# zhengbingquant_Nano_V1.net
KiCad netlist of a schematic drawn in EasyEDA Pro
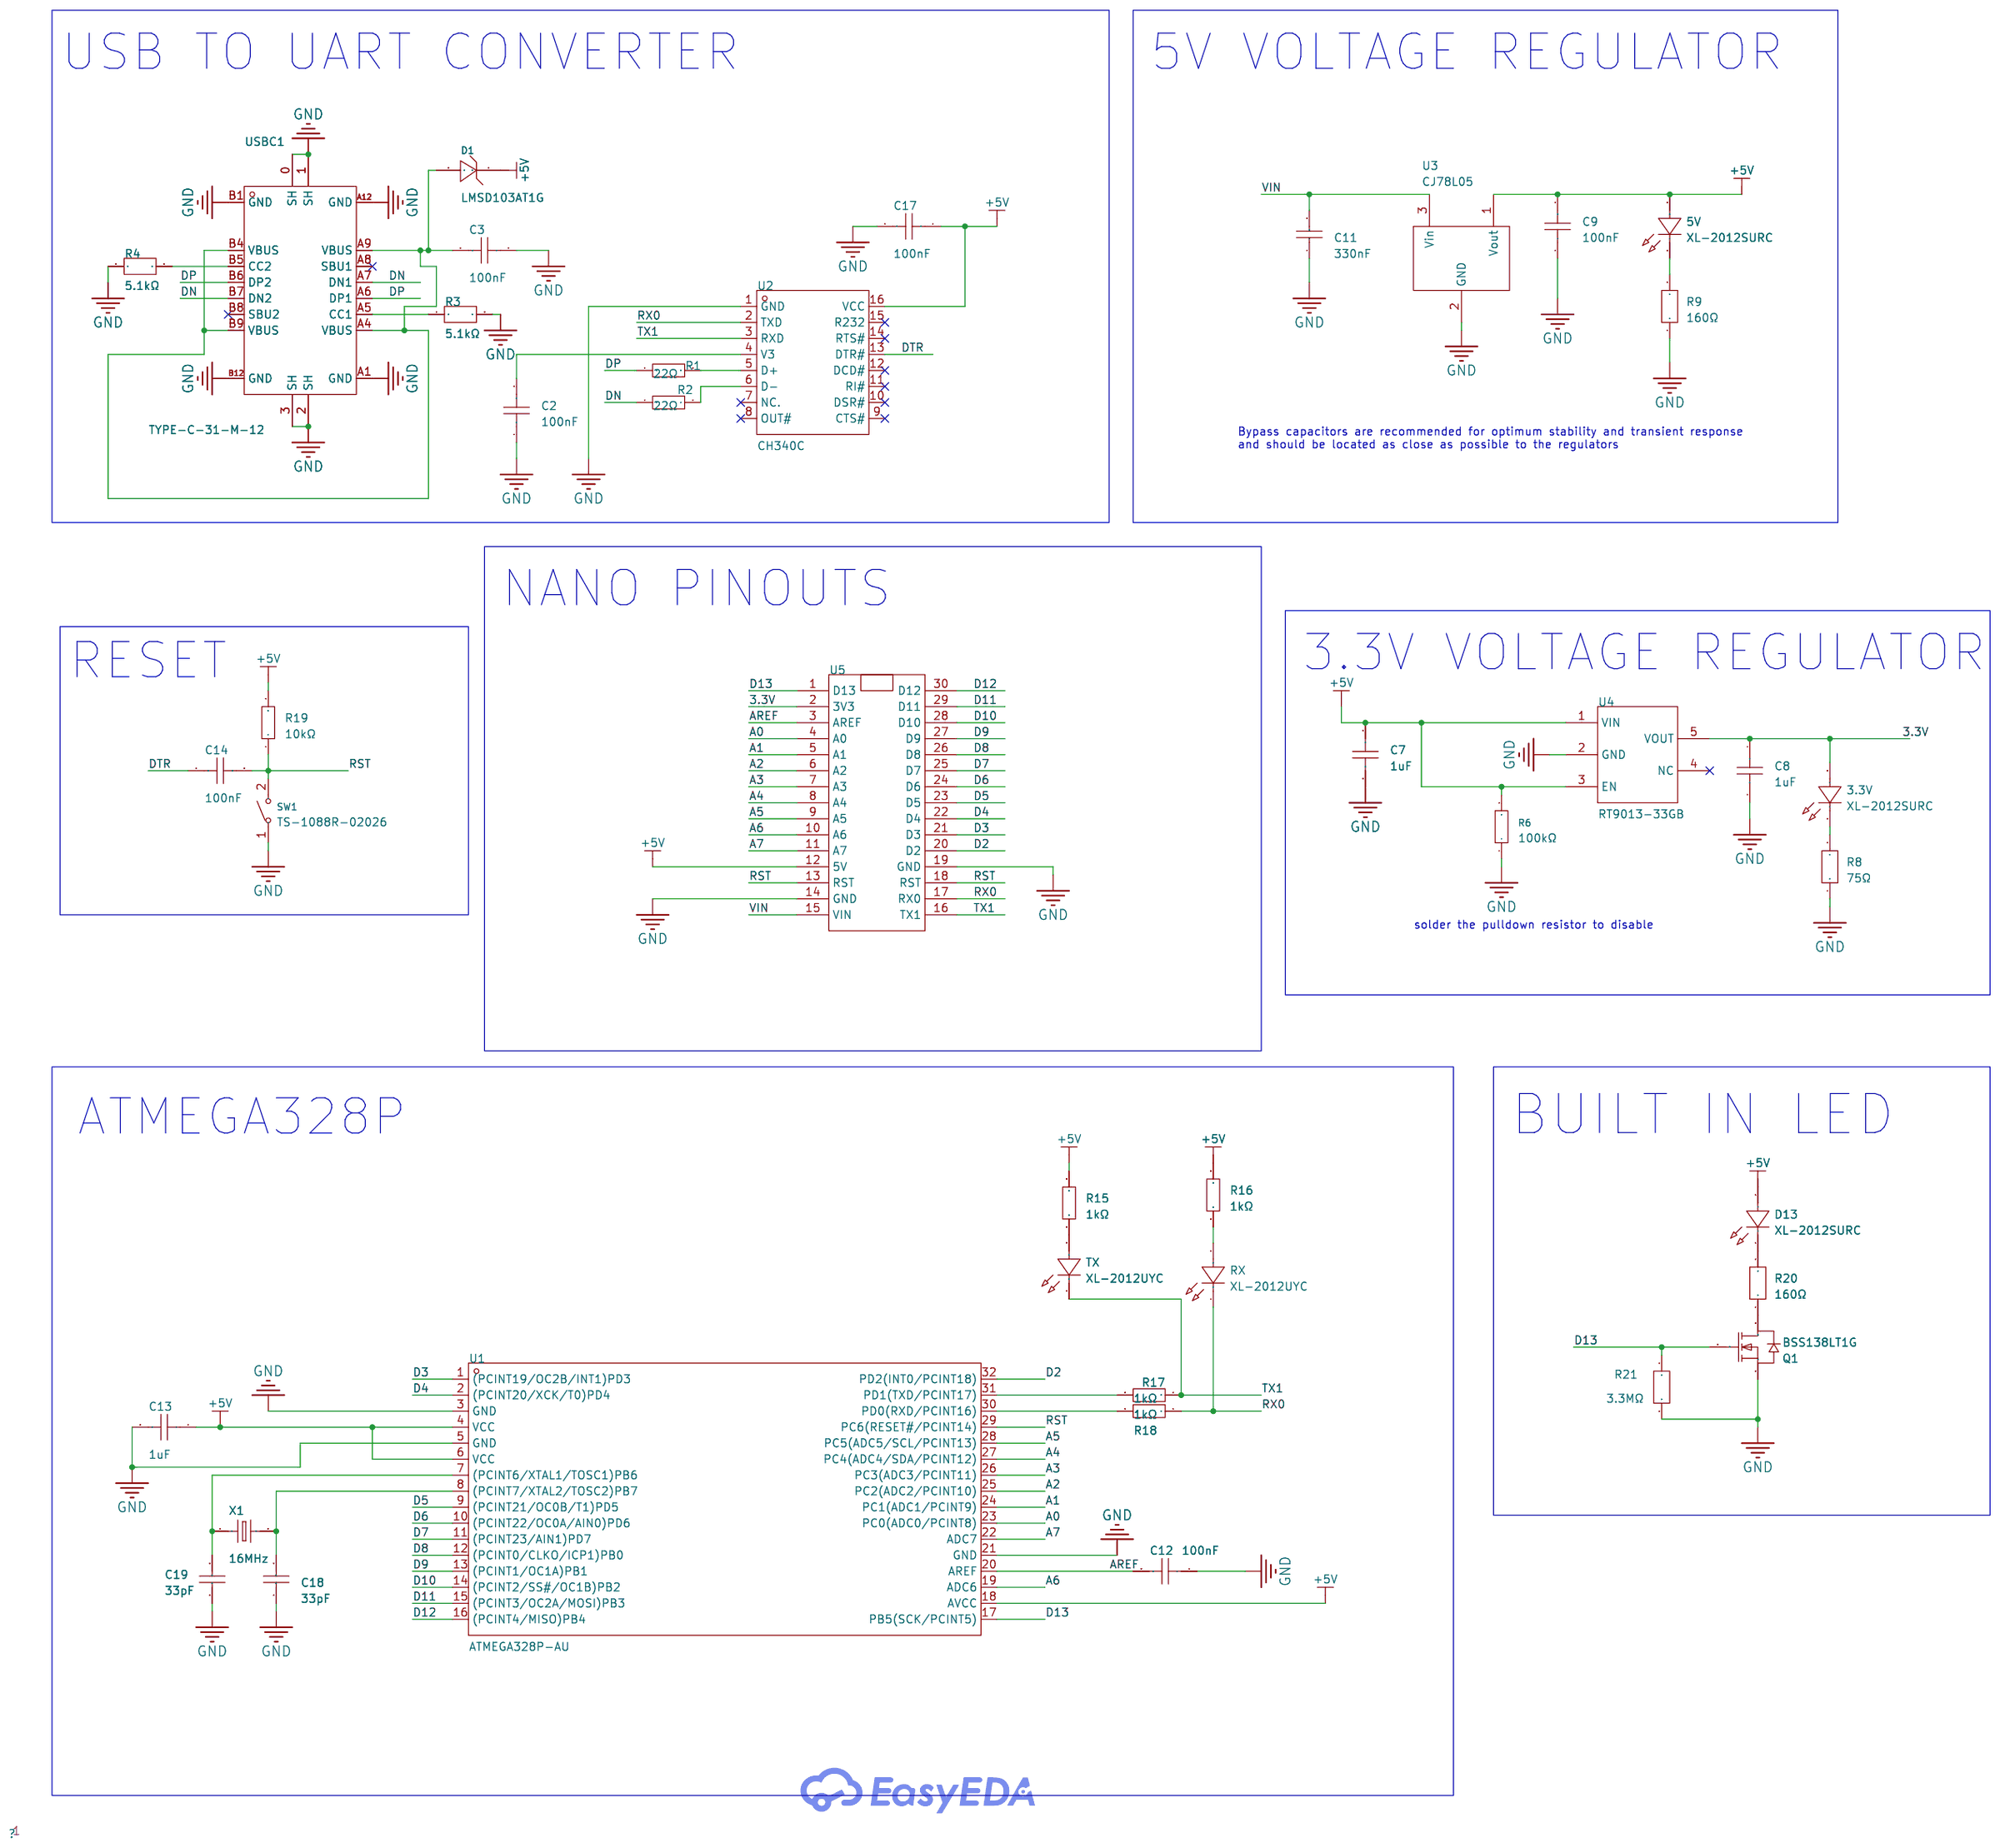
[diagram p0: schematic sheet]

(export (version "E")
  (design (tool "Eeschema 10.0.6"))
  (components
    (comp (ref "3.3V")
      (value "XL-2012SURC")
      (footprint "easyedapro:LED0805-RD_RED")
      (fields (field (name "Manufacturer") "XINGLIGHT(成兴光)"))
      (libsource (lib "easyedapro") (part "XL-2012SURC"))
    )
    (comp (ref "5V")
      (value "XL-2012SURC")
      (footprint "easyedapro:LED0805-RD_RED")
      (fields (field (name "Manufacturer") "XINGLIGHT(成兴光)"))
      (libsource (lib "easyedapro") (part "XL-2012SURC"))
    )
    (comp (ref "C2")
      (value "100nF")
      (footprint "easyedapro:C0805")
      (fields
        (field (name "Manufacturer Part") "CL21B104KBCWPNC")
        (field (name "Manufacturer") "SAMSUNG(三星)")
      )
      (libsource (lib "easyedapro") (part "CL21B104KBCWPNC"))
    )
    (comp (ref "C3")
      (value "100nF")
      (footprint "easyedapro:C0805")
      (fields
        (field (name "Manufacturer Part") "CL21B104KBCWPNC")
        (field (name "Manufacturer") "SAMSUNG(三星)")
      )
      (libsource (lib "easyedapro") (part "CL21B104KBCWPNC"))
    )
    (comp (ref "C7")
      (value "1uF")
      (footprint "easyedapro:C0805")
      (description "Capacitance:1uF Tolerance:±10% Tolerance:±10% Voltage Rating:50V Temperature Coefficient:X5R")
      (fields
        (field (name "Manufacturer Part") "UMK212BJ105KG-T")
        (field (name "Manufacturer") "TAIYO YUDEN(太诱)")
      )
      (libsource (lib "easyedapro") (part "UMK212BJ105KG-T"))
    )
    (comp (ref "C8")
      (value "1uF")
      (footprint "easyedapro:C0805")
      (description "Capacitance:1uF Tolerance:±10% Tolerance:±10% Voltage Rating:50V Temperature Coefficient:X5R")
      (fields
        (field (name "Manufacturer Part") "UMK212BJ105KG-T")
        (field (name "Manufacturer") "TAIYO YUDEN(太诱)")
      )
      (libsource (lib "easyedapro") (part "UMK212BJ105KG-T"))
    )
    (comp (ref "C9")
      (value "100nF")
      (footprint "easyedapro:C0805")
      (fields
        (field (name "Manufacturer Part") "CL21B104KBCWPNC")
        (field (name "Manufacturer") "SAMSUNG(三星)")
      )
      (libsource (lib "easyedapro") (part "CL21B104KBCWPNC"))
    )
    (comp (ref "C11")
      (value "330nF")
      (footprint "easyedapro:C0805")
      (fields
        (field (name "Manufacturer Part") "CL21B334KBFNNNE")
        (field (name "Manufacturer") "SAMSUNG(三星)")
      )
      (libsource (lib "easyedapro") (part "CL21B334KBFNNNE"))
    )
    (comp (ref "C12")
      (value "100nF")
      (footprint "easyedapro:C0805")
      (fields
        (field (name "Manufacturer Part") "CL21B104KBCWPNC")
        (field (name "Manufacturer") "SAMSUNG(三星)")
      )
      (libsource (lib "easyedapro") (part "CL21B104KBCWPNC"))
    )
    (comp (ref "C13")
      (value "1uF")
      (footprint "easyedapro:C0805")
      (description "Capacitance:1uF Tolerance:±10% Tolerance:±10% Voltage Rating:50V Temperature Coefficient:X5R")
      (fields
        (field (name "Manufacturer Part") "UMK212BJ105KG-T")
        (field (name "Manufacturer") "TAIYO YUDEN(太诱)")
      )
      (libsource (lib "easyedapro") (part "UMK212BJ105KG-T"))
    )
    (comp (ref "C14")
      (value "100nF")
      (footprint "easyedapro:C0805")
      (fields
        (field (name "Manufacturer Part") "CL21B104KBCWPNC")
        (field (name "Manufacturer") "SAMSUNG(三星)")
      )
      (libsource (lib "easyedapro") (part "CL21B104KBCWPNC"))
    )
    (comp (ref "C17")
      (value "100nF")
      (footprint "easyedapro:C0805")
      (fields
        (field (name "Manufacturer Part") "CL21B104KBCWPNC")
        (field (name "Manufacturer") "SAMSUNG(三星)")
      )
      (libsource (lib "easyedapro") (part "CL21B104KBCWPNC"))
    )
    (comp (ref "C18")
      (value "33pF")
      (footprint "easyedapro:C0805")
      (fields (field (name "Manufacturer Part") "0805CG330J500NT") (field (name "Manufacturer") "FH(风华)"))
      (libsource (lib "easyedapro") (part "0805CG330J500NT"))
    )
    (comp (ref "C19")
      (value "33pF")
      (footprint "easyedapro:C0805")
      (fields (field (name "Manufacturer Part") "0805CG330J500NT") (field (name "Manufacturer") "FH(风华)"))
      (libsource (lib "easyedapro") (part "0805CG330J500NT"))
    )
    (comp (ref "D1")
      (value "LMSD103AT1G")
      (footprint "easyedapro:SOD-123_L2.8-W1.8-LS3.7-RD")
      (fields (field (name "Manufacturer") "LRC(乐山无线电)"))
      (libsource (lib "easyedapro") (part "LMSD103AT1G"))
    )
    (comp (ref "D13")
      (value "XL-2012SURC")
      (footprint "easyedapro:LED0805-RD_RED")
      (fields (field (name "Manufacturer") "XINGLIGHT(成兴光)"))
      (libsource (lib "easyedapro") (part "XL-2012SURC"))
    )
    (comp (ref "Q1")
      (value "BSS138LT1G")
      (footprint "easyedapro:SOT-23-3_L2.9-W1.6-P1.90-LS2.8-BR")
      (fields (field (name "Manufacturer") "onsemi(安森美)"))
      (libsource (lib "easyedapro") (part "BSS138LT1G"))
    )
    (comp (ref "R1")
      (value "22Ω")
      (footprint "easyedapro:R0603")
      (fields
        (field (name "Manufacturer Part") "0603WAF220JT5E")
        (field (name "Manufacturer") "UNI-ROYAL(厚声)")
      )
      (libsource (lib "easyedapro") (part "0603WAF220JT5E"))
    )
    (comp (ref "R2")
      (value "22Ω")
      (footprint "easyedapro:R0603")
      (fields
        (field (name "Manufacturer Part") "0603WAF220JT5E")
        (field (name "Manufacturer") "UNI-ROYAL(厚声)")
      )
      (libsource (lib "easyedapro") (part "0603WAF220JT5E"))
    )
    (comp (ref "R3")
      (value "5.1kΩ")
      (footprint "easyedapro:R0603")
      (fields (field (name "Manufacturer Part") "FRC0603F5101TS") (field (name "Manufacturer") "FOJAN(富捷)"))
      (libsource (lib "easyedapro") (part "FRC0603F5101TS"))
    )
    (comp (ref "R4")
      (value "5.1kΩ")
      (footprint "easyedapro:R0603")
      (fields (field (name "Manufacturer Part") "FRC0603F5101TS") (field (name "Manufacturer") "FOJAN(富捷)"))
      (libsource (lib "easyedapro") (part "FRC0603F5101TS"))
    )
    (comp (ref "R6")
      (value "100kΩ")
      (footprint "easyedapro:R0805")
      (fields
        (field (name "Manufacturer Part") "0805W8F1003T5E")
        (field (name "Manufacturer") "UNI-ROYAL(厚声)")
      )
      (libsource (lib "easyedapro") (part "0805W8F1003T5E_C149504"))
    )
    (comp (ref "R8")
      (value "75Ω")
      (footprint "easyedapro:R0805")
      (fields (field (name "Manufacturer Part") "FRC0805J750 TS") (field (name "Manufacturer") "FOJAN(富捷)"))
      (libsource (lib "easyedapro") (part "FRC0805J750 TS"))
    )
    (comp (ref "R9")
      (value "160Ω")
      (footprint "easyedapro:R0805")
      (fields (field (name "Manufacturer Part") "FRC0805F1600TS") (field (name "Manufacturer") "FOJAN(富捷)"))
      (libsource (lib "easyedapro") (part "FRC0805F1600TS"))
    )
    (comp (ref "R15")
      (value "1kΩ")
      (footprint "easyedapro:R0805")
      (fields (field (name "Manufacturer Part") "RC0805FR-071KL") (field (name "Manufacturer") "YAGEO(国巨)"))
      (libsource (lib "easyedapro") (part "RC0805FR-071KL"))
    )
    (comp (ref "R16")
      (value "1kΩ")
      (footprint "easyedapro:R0805")
      (fields (field (name "Manufacturer Part") "RC0805FR-071KL") (field (name "Manufacturer") "YAGEO(国巨)"))
      (libsource (lib "easyedapro") (part "RC0805FR-071KL"))
    )
    (comp (ref "R17")
      (value "1kΩ")
      (footprint "easyedapro:R0805")
      (fields (field (name "Manufacturer Part") "RC0805FR-071KL") (field (name "Manufacturer") "YAGEO(国巨)"))
      (libsource (lib "easyedapro") (part "RC0805FR-071KL"))
    )
    (comp (ref "R18")
      (value "1kΩ")
      (footprint "easyedapro:R0805")
      (fields (field (name "Manufacturer Part") "RC0805FR-071KL") (field (name "Manufacturer") "YAGEO(国巨)"))
      (libsource (lib "easyedapro") (part "RC0805FR-071KL"))
    )
    (comp (ref "R19")
      (value "10kΩ")
      (footprint "easyedapro:R0805")
      (fields (field (name "Manufacturer Part") "RC0805FR-0710KL") (field (name "Manufacturer") "YAGEO(国巨)"))
      (libsource (lib "easyedapro") (part "RC0805FR-0710KL"))
    )
    (comp (ref "R20")
      (value "160Ω")
      (footprint "easyedapro:R0805")
      (fields (field (name "Manufacturer Part") "FRC0805F1600TS") (field (name "Manufacturer") "FOJAN(富捷)"))
      (libsource (lib "easyedapro") (part "FRC0805F1600TS"))
    )
    (comp (ref "R21")
      (value "3.3MΩ")
      (footprint "easyedapro:R0805")
      (fields (field (name "Manufacturer Part") "AC0805FR-073M3L") (field (name "Manufacturer") "YAGEO(国巨)"))
      (libsource (lib "easyedapro") (part "AC0805FR-073M3L"))
    )
    (comp (ref "RX")
      (value "XL-2012UYC")
      (footprint "easyedapro:LED0805-RD_YELLOW")
      (fields (field (name "Manufacturer") "XINGLIGHT(成兴光)"))
      (libsource (lib "easyedapro") (part "XL-2012UYC"))
    )
    (comp (ref "SW1")
      (value "TS-1088R-02026")
      (footprint "easyedapro:SW-SMD_L3.9-W3.0-P4.45")
      (fields (field (name "Manufacturer") "XUNPU(讯普)"))
      (libsource (lib "easyedapro") (part "TS-1088R-02026"))
    )
    (comp (ref "TX")
      (value "XL-2012UYC")
      (footprint "easyedapro:LED0805-RD_YELLOW")
      (fields (field (name "Manufacturer") "XINGLIGHT(成兴光)"))
      (libsource (lib "easyedapro") (part "XL-2012UYC"))
    )
    (comp (ref "U1")
      (value "ATMEGA328P-AU")
      (footprint "easyedapro:TQFP-32_L7.0-W7.0-P0.80-LS9.0-BL")
      (fields (field (name "Manufacturer") "MICROCHIP(美国微芯)"))
      (libsource (lib "easyedapro") (part "ATMEGA328P-AU"))
    )
    (comp (ref "U2")
      (value "CH340C")
      (footprint "easyedapro:SOP-16_L10.0-W3.9-P1.27-LS6.0-BL")
      (fields (field (name "Manufacturer") "WCH(南京沁恒)"))
      (libsource (lib "easyedapro") (part "CH340C"))
    )
    (comp (ref "U3")
      (value "CJ78L05")
      (footprint "easyedapro:SOT-89-3_L4.5-W2.5-P1.50-LS4.2-BR")
      (fields (field (name "Manufacturer") "CJ(江苏长电/长晶)"))
      (libsource (lib "easyedapro") (part "CJ78L05"))
    )
    (comp (ref "U4")
      (value "RT9013-33GB")
      (footprint "easyedapro:SOT-23-5_L3.0-W1.7-P0.95-LS2.8-BL")
      (fields (field (name "Manufacturer") "RICHTEK(立锜)"))
      (libsource (lib "easyedapro") (part "RT9013-33GB"))
    )
    (comp (ref "U5") (value "~") (libsource (lib "easyedapro") (part "Nano_pinout")))
    (comp (ref "USBC1")
      (value "TYPE-C-31-M-12")
      (footprint "easyedapro:USB-C_SMD-TYPE-C-31-M-12")
      (fields (field (name "Manufacturer") "韩国韩荣"))
      (libsource (lib "easyedapro") (part "TYPE-C-31-M-12"))
    )
    (comp (ref "X1")
      (value "16MHz")
      (footprint "easyedapro:HC-49US_L11.5-W4.5-P4.88")
      (fields
        (field (name "Manufacturer Part") "49S-16.000-20-20-20/A")
        (field (name "Manufacturer") "LIMING(利明)")
      )
      (libsource (lib "easyedapro") (part "49S-16.000-20-20-20/A"))
    )
  )
  (nets
    (net (code "1") (name "+5V") (class "Default")
      (node (ref "5V") (pin "2") (pinfunction "A_2") (pintype "unspecified"))
      (node (ref "C13") (pin "1") (pinfunction "1_1") (pintype "unspecified"))
      (node (ref "C17") (pin "1") (pinfunction "1_1") (pintype "input"))
      (node (ref "C7") (pin "1") (pinfunction "1_1") (pintype "unspecified"))
      (node (ref "C9") (pin "2") (pinfunction "2_2") (pintype "input"))
      (node (ref "D1") (pin "1") (pinfunction "C_1") (pintype "input"))
      (node (ref "D13") (pin "2") (pinfunction "A_2") (pintype "unspecified"))
      (node (ref "R15") (pin "2") (pinfunction "2_2") (pintype "input"))
      (node (ref "R16") (pin "2") (pinfunction "2_2") (pintype "input"))
      (node (ref "R19") (pin "2") (pinfunction "2_2") (pintype "input"))
      (node (ref "R6") (pin "2") (pinfunction "2_2") (pintype "input"))
      (node (ref "U1") (pin "18") (pinfunction "AVCC_18") (pintype "unspecified"))
      (node (ref "U1") (pin "4") (pinfunction "VCC_4") (pintype "unspecified"))
      (node (ref "U1") (pin "6") (pinfunction "VCC_6") (pintype "unspecified"))
      (node (ref "U2") (pin "16") (pinfunction "VCC_16") (pintype "unspecified"))
      (node (ref "U3") (pin "1") (pinfunction "Vout_1") (pintype "unspecified"))
      (node (ref "U4") (pin "1") (pinfunction "VIN_1") (pintype "unspecified"))
      (node (ref "U4") (pin "3") (pinfunction "EN_3") (pintype "unspecified"))
      (node (ref "U5") (pin "12") (pinfunction "5V_12") (pintype "input"))
    )
    (net (code "2") (name "/3.3V") (class "Default")
      (node (ref "3.3V") (pin "2") (pinfunction "A_2") (pintype "unspecified"))
      (node (ref "C8") (pin "1") (pinfunction "1_1") (pintype "unspecified"))
      (node (ref "U4") (pin "5") (pinfunction "VOUT_5") (pintype "unspecified"))
      (node (ref "U5") (pin "2") (pinfunction "3V3_2") (pintype "input"))
    )
    (net (code "3") (name "/A0") (class "Default")
      (node (ref "U1") (pin "23") (pinfunction "PC0(ADC0/PCINT8)_23") (pintype "unspecified"))
      (node (ref "U5") (pin "4") (pinfunction "A0_4") (pintype "input"))
    )
    (net (code "4") (name "/A1") (class "Default")
      (node (ref "U1") (pin "24") (pinfunction "PC1(ADC1/PCINT9)_24") (pintype "unspecified"))
      (node (ref "U5") (pin "5") (pinfunction "A1_5") (pintype "input"))
    )
    (net (code "5") (name "/A2") (class "Default")
      (node (ref "U1") (pin "25") (pinfunction "PC2(ADC2/PCINT10)_25") (pintype "unspecified"))
      (node (ref "U5") (pin "6") (pinfunction "A2_6") (pintype "input"))
    )
    (net (code "6") (name "/A3") (class "Default")
      (node (ref "U1") (pin "26") (pinfunction "PC3(ADC3/PCINT11)_26") (pintype "unspecified"))
      (node (ref "U5") (pin "7") (pinfunction "A3_7") (pintype "input"))
    )
    (net (code "7") (name "/A4") (class "Default")
      (node (ref "U1") (pin "27") (pinfunction "PC4(ADC4/SDA/PCINT12)_27") (pintype "unspecified"))
      (node (ref "U5") (pin "8") (pinfunction "A4_8") (pintype "input"))
    )
    (net (code "8") (name "/A5") (class "Default")
      (node (ref "U1") (pin "28") (pinfunction "PC5(ADC5/SCL/PCINT13)_28") (pintype "unspecified"))
      (node (ref "U5") (pin "9") (pinfunction "A5_9") (pintype "input"))
    )
    (net (code "9") (name "/A6") (class "Default")
      (node (ref "U1") (pin "19") (pinfunction "ADC6_19") (pintype "unspecified"))
      (node (ref "U5") (pin "10") (pinfunction "A6_10") (pintype "input"))
    )
    (net (code "10") (name "/A7") (class "Default")
      (node (ref "U1") (pin "22") (pinfunction "ADC7_22") (pintype "unspecified"))
      (node (ref "U5") (pin "11") (pinfunction "A7_11") (pintype "input"))
    )
    (net (code "11") (name "/AREF") (class "Default")
      (node (ref "C12") (pin "2") (pinfunction "2_2") (pintype "input"))
      (node (ref "U1") (pin "20") (pinfunction "AREF_20") (pintype "unspecified"))
      (node (ref "U5") (pin "3") (pinfunction "AREF_3") (pintype "input"))
    )
    (net (code "12") (name "/D2") (class "Default")
      (node (ref "U1") (pin "32") (pinfunction "PD2(INT0/PCINT18)_32") (pintype "unspecified"))
      (node (ref "U5") (pin "20") (pinfunction "D2_20") (pintype "input"))
    )
    (net (code "13") (name "/D3") (class "Default")
      (node (ref "U1") (pin "1") (pinfunction "(PCINT19/OC2B/INT1)PD3_1") (pintype "unspecified"))
      (node (ref "U5") (pin "21") (pinfunction "D3_21") (pintype "input"))
    )
    (net (code "14") (name "/D4") (class "Default")
      (node (ref "U1") (pin "2") (pinfunction "(PCINT20/XCK/T0)PD4_2") (pintype "unspecified"))
      (node (ref "U5") (pin "22") (pinfunction "D4_22") (pintype "input"))
    )
    (net (code "15") (name "/D5") (class "Default")
      (node (ref "U1") (pin "9") (pinfunction "(PCINT21/OC0B/T1)PD5_9") (pintype "unspecified"))
      (node (ref "U5") (pin "23") (pinfunction "D5_23") (pintype "input"))
    )
    (net (code "16") (name "/D6") (class "Default")
      (node (ref "U1") (pin "10") (pinfunction "(PCINT22/OC0A/AIN0)PD6_10") (pintype "unspecified"))
      (node (ref "U5") (pin "24") (pinfunction "D6_24") (pintype "input"))
    )
    (net (code "17") (name "/D7") (class "Default")
      (node (ref "U1") (pin "11") (pinfunction "(PCINT23/AIN1)PD7_11") (pintype "unspecified"))
      (node (ref "U5") (pin "25") (pinfunction "D7_25") (pintype "input"))
    )
    (net (code "18") (name "/D8") (class "Default")
      (node (ref "U1") (pin "12") (pinfunction "(PCINT0/CLKO/ICP1)PB0_12") (pintype "unspecified"))
      (node (ref "U5") (pin "26") (pinfunction "D8_26") (pintype "input"))
    )
    (net (code "19") (name "/D9") (class "Default")
      (node (ref "U1") (pin "13") (pinfunction "(PCINT1/OC1A)PB1_13") (pintype "unspecified"))
      (node (ref "U5") (pin "27") (pinfunction "D9_27") (pintype "input"))
    )
    (net (code "20") (name "/D10") (class "Default")
      (node (ref "U1") (pin "14") (pinfunction "(PCINT2/SS#/OC1B)PB2_14") (pintype "unspecified"))
      (node (ref "U5") (pin "28") (pinfunction "D10_28") (pintype "input"))
    )
    (net (code "21") (name "/D11") (class "Default")
      (node (ref "U1") (pin "15") (pinfunction "(PCINT3/OC2A/MOSI)PB3_15") (pintype "unspecified"))
      (node (ref "U5") (pin "29") (pinfunction "D11_29") (pintype "input"))
    )
    (net (code "22") (name "/D12") (class "Default")
      (node (ref "U1") (pin "16") (pinfunction "(PCINT4/MISO)PB4_16") (pintype "unspecified"))
      (node (ref "U5") (pin "30") (pinfunction "D12_30") (pintype "input"))
    )
    (net (code "23") (name "/D13") (class "Default")
      (node (ref "Q1") (pin "1") (pinfunction "G_1") (pintype "unspecified"))
      (node (ref "R21") (pin "1") (pinfunction "1_1") (pintype "unspecified"))
      (node (ref "U1") (pin "17") (pinfunction "PB5(SCK/PCINT5)_17") (pintype "unspecified"))
      (node (ref "U5") (pin "1") (pinfunction "D13_1") (pintype "input"))
    )
    (net (code "24") (name "/DN") (class "Default")
      (node (ref "R2") (pin "1") (pinfunction "1_1") (pintype "input"))
      (node (ref "USBC1") (pin "A7") (pinfunction "DN1_A7") (pintype "unspecified"))
      (node (ref "USBC1") (pin "B7") (pinfunction "DN2_B7") (pintype "unspecified"))
    )
    (net (code "25") (name "/DP") (class "Default")
      (node (ref "R1") (pin "1") (pinfunction "1_1") (pintype "input"))
      (node (ref "USBC1") (pin "A6") (pinfunction "DP1_A6") (pintype "unspecified"))
      (node (ref "USBC1") (pin "B6") (pinfunction "DP2_B6") (pintype "unspecified"))
    )
    (net (code "26") (name "/DTR") (class "Default")
      (node (ref "C14") (pin "1") (pinfunction "1_1") (pintype "input"))
      (node (ref "U2") (pin "13") (pinfunction "DTR#_13") (pintype "unspecified"))
    )
    (net (code "27") (name "/RST") (class "Default")
      (node (ref "C14") (pin "2") (pinfunction "2_2") (pintype "input"))
      (node (ref "R19") (pin "1") (pinfunction "1_1") (pintype "input"))
      (node (ref "SW1") (pin "2") (pinfunction "2_2") (pintype "input"))
      (node (ref "U1") (pin "29") (pinfunction "PC6(RESET#/PCINT14)_29") (pintype "unspecified"))
      (node (ref "U5") (pin "13") (pinfunction "RST_13") (pintype "input"))
      (node (ref "U5") (pin "18") (pinfunction "RST_18") (pintype "input"))
    )
    (net (code "28") (name "/RX0") (class "Default")
      (node (ref "R18") (pin "1") (pinfunction "1_1") (pintype "input"))
      (node (ref "RX") (pin "1") (pinfunction "K_1") (pintype "unspecified"))
      (node (ref "U2") (pin "2") (pinfunction "TXD_2") (pintype "unspecified"))
      (node (ref "U5") (pin "17") (pinfunction "RX0_17") (pintype "input"))
    )
    (net (code "29") (name "/TX1") (class "Default")
      (node (ref "R17") (pin "1") (pinfunction "1_1") (pintype "input"))
      (node (ref "TX") (pin "1") (pinfunction "K_1") (pintype "unspecified"))
      (node (ref "U2") (pin "3") (pinfunction "RXD_3") (pintype "unspecified"))
      (node (ref "U5") (pin "16") (pinfunction "TX1_16") (pintype "input"))
    )
    (net (code "30") (name "/VIN") (class "Default")
      (node (ref "C11") (pin "2") (pinfunction "2_2") (pintype "input"))
      (node (ref "U3") (pin "3") (pinfunction "Vin_3") (pintype "unspecified"))
      (node (ref "U5") (pin "15") (pinfunction "VIN_15") (pintype "input"))
    )
    (net (code "31") (name "GND") (class "Default")
      (node (ref "C11") (pin "1") (pinfunction "1_1") (pintype "input"))
      (node (ref "C12") (pin "1") (pinfunction "1_1") (pintype "input"))
      (node (ref "C13") (pin "2") (pinfunction "2_2") (pintype "unspecified"))
      (node (ref "C17") (pin "2") (pinfunction "2_2") (pintype "input"))
      (node (ref "C18") (pin "1") (pinfunction "1_1") (pintype "input"))
      (node (ref "C19") (pin "1") (pinfunction "1_1") (pintype "input"))
      (node (ref "C2") (pin "1") (pinfunction "1_1") (pintype "input"))
      (node (ref "C3") (pin "1") (pinfunction "1_1") (pintype "input"))
      (node (ref "C7") (pin "2") (pinfunction "2_2") (pintype "unspecified"))
      (node (ref "C8") (pin "2") (pinfunction "2_2") (pintype "unspecified"))
      (node (ref "C9") (pin "1") (pinfunction "1_1") (pintype "input"))
      (node (ref "Q1") (pin "2") (pinfunction "S_2") (pintype "unspecified"))
      (node (ref "R21") (pin "2") (pinfunction "2_2") (pintype "unspecified"))
      (node (ref "R3") (pin "2") (pinfunction "2_2") (pintype "unspecified"))
      (node (ref "R4") (pin "2") (pinfunction "2_2") (pintype "unspecified"))
      (node (ref "R6") (pin "1") (pinfunction "1_1") (pintype "input"))
      (node (ref "R8") (pin "1") (pinfunction "1_1") (pintype "unspecified"))
      (node (ref "R9") (pin "1") (pinfunction "1_1") (pintype "unspecified"))
      (node (ref "SW1") (pin "1") (pinfunction "1_1") (pintype "input"))
      (node (ref "U1") (pin "21") (pinfunction "GND_21") (pintype "unspecified"))
      (node (ref "U1") (pin "3") (pinfunction "GND_3") (pintype "unspecified"))
      (node (ref "U1") (pin "5") (pinfunction "GND_5") (pintype "unspecified"))
      (node (ref "U2") (pin "1") (pinfunction "GND_1") (pintype "unspecified"))
      (node (ref "U3") (pin "2") (pinfunction "GND_2") (pintype "unspecified"))
      (node (ref "U4") (pin "2") (pinfunction "GND_2") (pintype "unspecified"))
      (node (ref "U5") (pin "14") (pinfunction "GND_14") (pintype "input"))
      (node (ref "U5") (pin "19") (pinfunction "GND_19") (pintype "input"))
      (node (ref "USBC1") (pin "0") (pinfunction "SH_0") (pintype "unspecified"))
      (node (ref "USBC1") (pin "1") (pinfunction "SH_1") (pintype "unspecified"))
      (node (ref "USBC1") (pin "2") (pinfunction "SH_2") (pintype "unspecified"))
      (node (ref "USBC1") (pin "3") (pinfunction "SH_3") (pintype "unspecified"))
      (node (ref "USBC1") (pin "A1") (pinfunction "GND_A1") (pintype "unspecified"))
      (node (ref "USBC1") (pin "A12") (pinfunction "GND_A12") (pintype "unspecified"))
      (node (ref "USBC1") (pin "B1") (pinfunction "GND_B1") (pintype "unspecified"))
      (node (ref "USBC1") (pin "B12") (pinfunction "GND_B12") (pintype "unspecified"))
    )
    (net (code "32") (name "Net-(3.3V-K)") (class "Default")
      (node (ref "3.3V") (pin "1") (pinfunction "K_1") (pintype "unspecified"))
      (node (ref "R8") (pin "2") (pinfunction "2_2") (pintype "unspecified"))
    )
    (net (code "33") (name "Net-(5V-K)") (class "Default")
      (node (ref "5V") (pin "1") (pinfunction "K_1") (pintype "unspecified"))
      (node (ref "R9") (pin "2") (pinfunction "2_2") (pintype "unspecified"))
    )
    (net (code "34") (name "Net-(D1-A)") (class "Default")
      (node (ref "C3") (pin "2") (pinfunction "2_2") (pintype "input"))
      (node (ref "D1") (pin "2") (pinfunction "A_2") (pintype "input"))
      (node (ref "USBC1") (pin "A4") (pinfunction "VBUS_A4") (pintype "unspecified"))
      (node (ref "USBC1") (pin "A9") (pinfunction "VBUS_A9") (pintype "unspecified"))
      (node (ref "USBC1") (pin "B4") (pinfunction "VBUS_B4") (pintype "unspecified"))
      (node (ref "USBC1") (pin "B9") (pinfunction "VBUS_B9") (pintype "unspecified"))
    )
    (net (code "35") (name "Net-(D13-K)") (class "Default")
      (node (ref "D13") (pin "1") (pinfunction "K_1") (pintype "unspecified"))
      (node (ref "R20") (pin "2") (pinfunction "2_2") (pintype "unspecified"))
    )
    (net (code "36") (name "Net-(Q1-D)") (class "Default")
      (node (ref "Q1") (pin "3") (pinfunction "D_3") (pintype "unspecified"))
      (node (ref "R20") (pin "1") (pinfunction "1_1") (pintype "unspecified"))
    )
    (net (code "37") (name "Net-(RX-A)") (class "Default")
      (node (ref "R16") (pin "1") (pinfunction "1_1") (pintype "input"))
      (node (ref "RX") (pin "2") (pinfunction "A_2") (pintype "unspecified"))
    )
    (net (code "38") (name "Net-(TX-A)") (class "Default")
      (node (ref "R15") (pin "1") (pinfunction "1_1") (pintype "input"))
      (node (ref "TX") (pin "2") (pinfunction "A_2") (pintype "unspecified"))
    )
    (net (code "39") (name "Net-(U1-(PCINT6{slash}XTAL1{slash}TOSC1)PB6)") (class "Default")
      (node (ref "C19") (pin "2") (pinfunction "2_2") (pintype "input"))
      (node (ref "U1") (pin "7") (pinfunction "(PCINT6/XTAL1/TOSC1)PB6_7") (pintype "unspecified"))
      (node (ref "X1") (pin "1") (pinfunction "1_1") (pintype "unspecified"))
    )
    (net (code "40") (name "Net-(U1-(PCINT7{slash}XTAL2{slash}TOSC2)PB7)") (class "Default")
      (node (ref "C18") (pin "2") (pinfunction "2_2") (pintype "input"))
      (node (ref "U1") (pin "8") (pinfunction "(PCINT7/XTAL2/TOSC2)PB7_8") (pintype "unspecified"))
      (node (ref "X1") (pin "2") (pinfunction "2_2") (pintype "unspecified"))
    )
    (net (code "41") (name "Net-(U1-PD0(RXD{slash}PCINT16))") (class "Default")
      (node (ref "R18") (pin "2") (pinfunction "2_2") (pintype "input"))
      (node (ref "U1") (pin "30") (pinfunction "PD0(RXD/PCINT16)_30") (pintype "unspecified"))
    )
    (net (code "42") (name "Net-(U1-PD1(TXD{slash}PCINT17))") (class "Default")
      (node (ref "R17") (pin "2") (pinfunction "2_2") (pintype "input"))
      (node (ref "U1") (pin "31") (pinfunction "PD1(TXD/PCINT17)_31") (pintype "unspecified"))
    )
    (net (code "43") (name "Net-(U2-D+)") (class "Default")
      (node (ref "R1") (pin "2") (pinfunction "2_2") (pintype "input"))
      (node (ref "U2") (pin "5") (pinfunction "D+_5") (pintype "unspecified"))
    )
    (net (code "44") (name "Net-(U2-D-)") (class "Default")
      (node (ref "R2") (pin "2") (pinfunction "2_2") (pintype "input"))
      (node (ref "U2") (pin "6") (pinfunction "D-_6") (pintype "unspecified"))
    )
    (net (code "45") (name "Net-(U2-V3)") (class "Default")
      (node (ref "C2") (pin "2") (pinfunction "2_2") (pintype "input"))
      (node (ref "U2") (pin "4") (pinfunction "V3_4") (pintype "unspecified"))
    )
    (net (code "46") (name "Net-(USBC1-CC1)") (class "Default")
      (node (ref "R3") (pin "1") (pinfunction "1_1") (pintype "unspecified"))
      (node (ref "USBC1") (pin "A5") (pinfunction "CC1_A5") (pintype "unspecified"))
    )
    (net (code "47") (name "Net-(USBC1-CC2)") (class "Default")
      (node (ref "R4") (pin "1") (pinfunction "1_1") (pintype "unspecified"))
      (node (ref "USBC1") (pin "B5") (pinfunction "CC2_B5") (pintype "unspecified"))
    )
    (net (code "48") (name "unconnected-(U2-CTS#-Pad9)") (class "Default")
      (node (ref "U2") (pin "9") (pinfunction "CTS#_9") (pintype "unspecified+no_connect"))
    )
    (net (code "49") (name "unconnected-(U2-DCD#-Pad12)") (class "Default")
      (node (ref "U2") (pin "12") (pinfunction "DCD#_12") (pintype "unspecified+no_connect"))
    )
    (net (code "50") (name "unconnected-(U2-DSR#-Pad10)") (class "Default")
      (node (ref "U2") (pin "10") (pinfunction "DSR#_10") (pintype "unspecified+no_connect"))
    )
    (net (code "51") (name "unconnected-(U2-NC.-Pad7)") (class "Default")
      (node (ref "U2") (pin "7") (pinfunction "NC._7") (pintype "unspecified+no_connect"))
    )
    (net (code "52") (name "unconnected-(U2-OUT#-Pad8)") (class "Default")
      (node (ref "U2") (pin "8") (pinfunction "OUT#_8") (pintype "unspecified+no_connect"))
    )
    (net (code "53") (name "unconnected-(U2-R232-Pad15)") (class "Default")
      (node (ref "U2") (pin "15") (pinfunction "R232_15") (pintype "unspecified+no_connect"))
    )
    (net (code "54") (name "unconnected-(U2-RI#-Pad11)") (class "Default")
      (node (ref "U2") (pin "11") (pinfunction "RI#_11") (pintype "unspecified+no_connect"))
    )
    (net (code "55") (name "unconnected-(U2-RTS#-Pad14)") (class "Default")
      (node (ref "U2") (pin "14") (pinfunction "RTS#_14") (pintype "unspecified+no_connect"))
    )
    (net (code "56") (name "unconnected-(U4-NC-Pad4)") (class "Default")
      (node (ref "U4") (pin "4") (pinfunction "NC_4") (pintype "unspecified+no_connect"))
    )
    (net (code "57") (name "unconnected-(USBC1-SBU1-PadA8)") (class "Default")
      (node (ref "USBC1") (pin "A8") (pinfunction "SBU1_A8") (pintype "unspecified+no_connect"))
    )
    (net (code "58") (name "unconnected-(USBC1-SBU2-PadB8)") (class "Default")
      (node (ref "USBC1") (pin "B8") (pinfunction "SBU2_B8") (pintype "unspecified+no_connect"))
    )
  )
)
